# SCH_Term_Digital_2025-01-27.net
KiCad netlist of a schematic drawn in EasyEDA
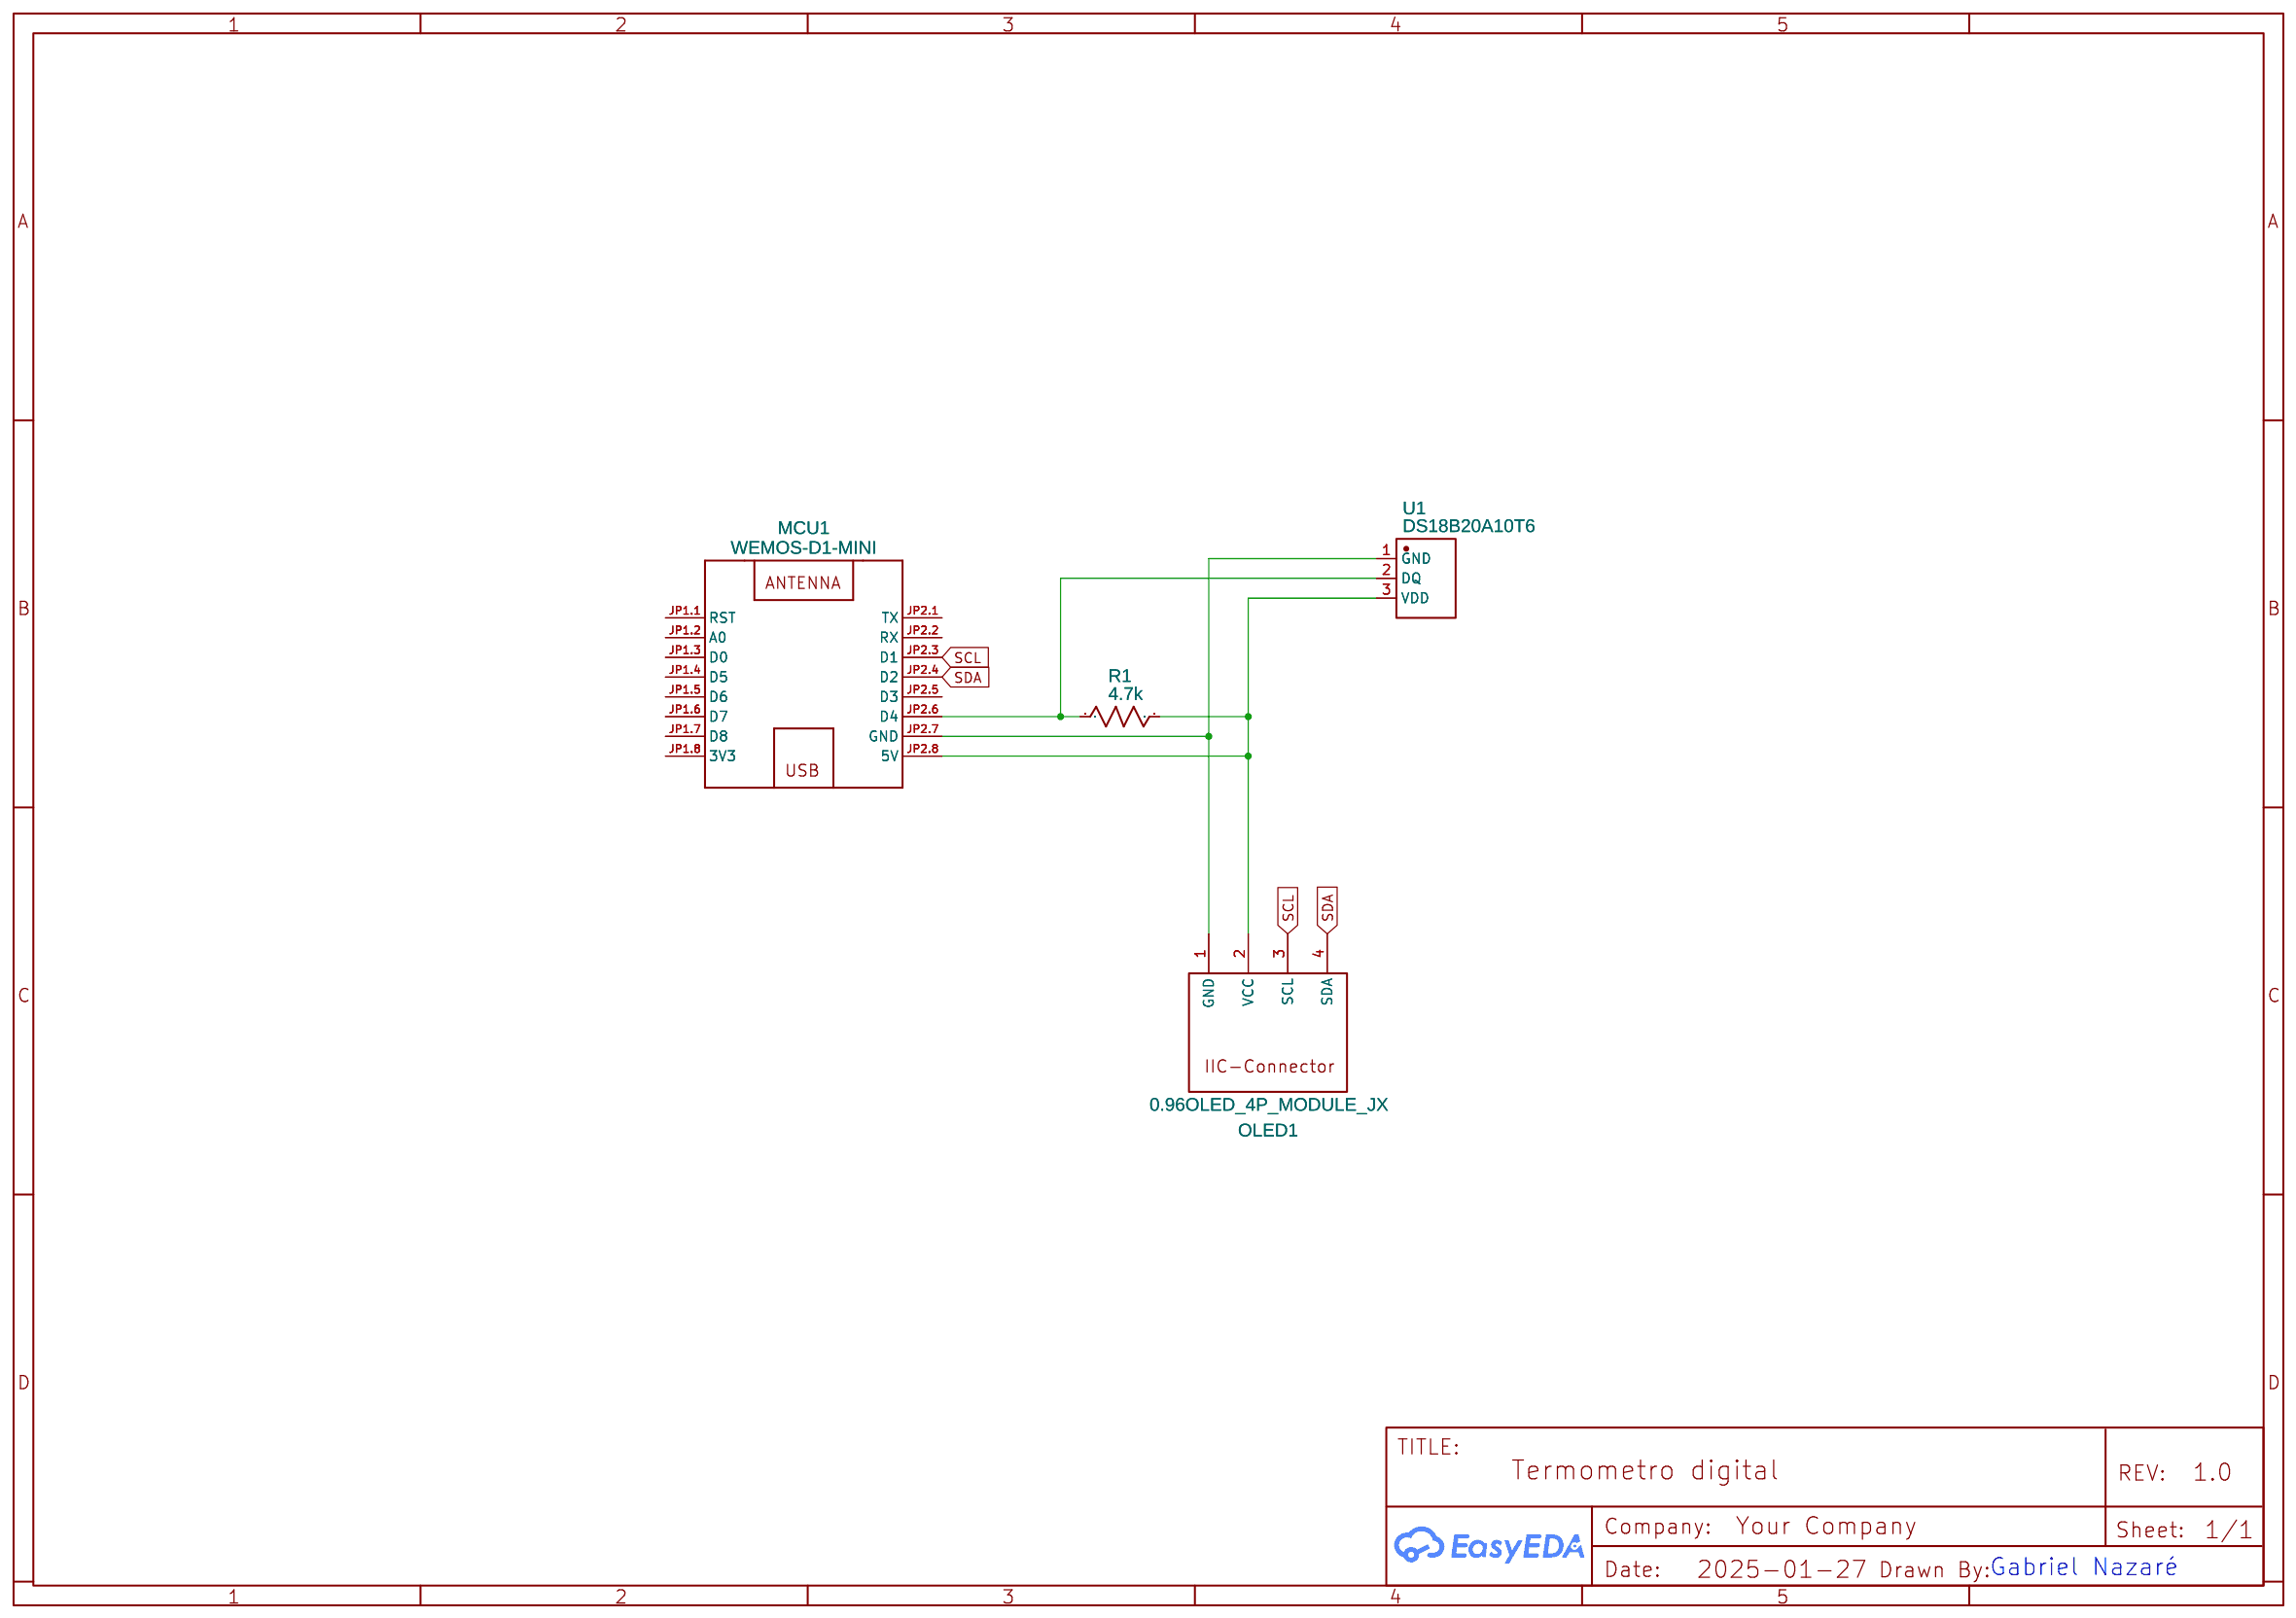
[diagram p0: schematic sheet]

(export (version "E")
  (design (tool "Eeschema 10.0.6"))
  (components
    (comp (ref "MCU1") (value "WEMOS-D1-MINI") (libsource (lib "") (part "WEMOS-D1-MINI")))
    (comp (ref "OLED1") (value "0.96OLED_4P_MODULE_JX") (libsource (lib "") (part "0.96OLED_4P_MODULE_JX")))
    (comp (ref "R1") (value "4.7k") (libsource (lib "") (part "R_0603_US")))
    (comp (ref "U1")
      (value "DS18B20A10T6")
      (fields (field (name "Manufacturer") "Mysentech(敏源传感)"))
      (libsource (lib "") (part "DS18B20A10T6"))
    )
  )
  (nets
    (net (code "1") (name "Net-(MCU1-5V)") (class "Default")
      (node (ref "MCU1") (pin "JP2.8") (pinfunction "5V_JP2.8") (pintype "bidirectional"))
      (node (ref "OLED1") (pin "2") (pinfunction "VCC_2") (pintype "unspecified"))
      (node (ref "R1") (pin "2") (pinfunction "2_2") (pintype "unspecified"))
      (node (ref "U1") (pin "3") (pinfunction "VDD_3") (pintype "unspecified"))
    )
    (net (code "2") (name "Net-(MCU1-D4)") (class "Default")
      (node (ref "MCU1") (pin "JP2.6") (pinfunction "D4_JP2.6") (pintype "bidirectional"))
      (node (ref "R1") (pin "1") (pinfunction "1_1") (pintype "unspecified"))
      (node (ref "U1") (pin "2") (pinfunction "DQ_2") (pintype "unspecified"))
    )
    (net (code "3") (name "Net-(MCU1-GND)") (class "Default")
      (node (ref "MCU1") (pin "JP2.7") (pinfunction "GND_JP2.7") (pintype "bidirectional"))
      (node (ref "OLED1") (pin "1") (pinfunction "GND_1") (pintype "unspecified"))
      (node (ref "U1") (pin "1") (pinfunction "GND_1") (pintype "unspecified"))
    )
    (net (code "4") (name "SCL") (class "Default")
      (node (ref "MCU1") (pin "JP2.3") (pinfunction "D1_JP2.3") (pintype "bidirectional"))
      (node (ref "OLED1") (pin "3") (pinfunction "SCL_3") (pintype "unspecified"))
    )
    (net (code "5") (name "SDA") (class "Default")
      (node (ref "MCU1") (pin "JP2.4") (pinfunction "D2_JP2.4") (pintype "bidirectional"))
      (node (ref "OLED1") (pin "4") (pinfunction "SDA_4") (pintype "unspecified"))
    )
    (net (code "6") (name "unconnected-(MCU1-3V3-PadJP1.8)") (class "Default")
      (node (ref "MCU1") (pin "JP1.8") (pinfunction "3V3_JP1.8") (pintype "bidirectional"))
    )
    (net (code "7") (name "unconnected-(MCU1-A0-PadJP1.2)") (class "Default")
      (node (ref "MCU1") (pin "JP1.2") (pinfunction "A0_JP1.2") (pintype "bidirectional"))
    )
    (net (code "8") (name "unconnected-(MCU1-D0-PadJP1.3)") (class "Default")
      (node (ref "MCU1") (pin "JP1.3") (pinfunction "D0_JP1.3") (pintype "bidirectional"))
    )
    (net (code "9") (name "unconnected-(MCU1-D3-PadJP2.5)") (class "Default")
      (node (ref "MCU1") (pin "JP2.5") (pinfunction "D3_JP2.5") (pintype "bidirectional"))
    )
    (net (code "10") (name "unconnected-(MCU1-D5-PadJP1.4)") (class "Default")
      (node (ref "MCU1") (pin "JP1.4") (pinfunction "D5_JP1.4") (pintype "bidirectional"))
    )
    (net (code "11") (name "unconnected-(MCU1-D6-PadJP1.5)") (class "Default")
      (node (ref "MCU1") (pin "JP1.5") (pinfunction "D6_JP1.5") (pintype "bidirectional"))
    )
    (net (code "12") (name "unconnected-(MCU1-D7-PadJP1.6)") (class "Default")
      (node (ref "MCU1") (pin "JP1.6") (pinfunction "D7_JP1.6") (pintype "bidirectional"))
    )
    (net (code "13") (name "unconnected-(MCU1-D8-PadJP1.7)") (class "Default")
      (node (ref "MCU1") (pin "JP1.7") (pinfunction "D8_JP1.7") (pintype "bidirectional"))
    )
    (net (code "14") (name "unconnected-(MCU1-RST-PadJP1.1)") (class "Default")
      (node (ref "MCU1") (pin "JP1.1") (pinfunction "RST_JP1.1") (pintype "bidirectional"))
    )
    (net (code "15") (name "unconnected-(MCU1-RX-PadJP2.2)") (class "Default")
      (node (ref "MCU1") (pin "JP2.2") (pinfunction "RX_JP2.2") (pintype "bidirectional"))
    )
    (net (code "16") (name "unconnected-(MCU1-TX-PadJP2.1)") (class "Default")
      (node (ref "MCU1") (pin "JP2.1") (pinfunction "TX_JP2.1") (pintype "bidirectional"))
    )
  )
)
